# POWER.net
KiCad netlist of a schematic drawn in Altium Designer
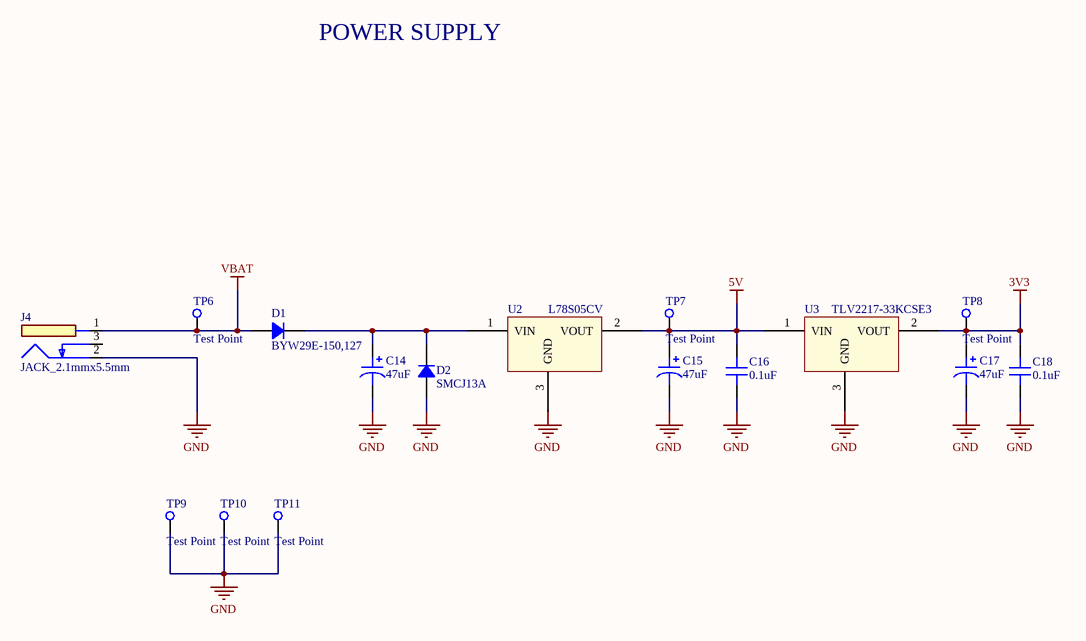
[diagram p0: POWER.SchDoc]

(export (version "E")
  (design (tool "Eeschema 10.0.6"))
  (components
    (comp (ref "C14")
      (value "47uF")
      (footprint "CAP_POL_D6.3MM_L5.8MM_H6.6MM")
      (description "CAP 47UF 35V ELECT WT SMD D6.3MM L5.8MM H 6.6MM")
      (fields (field (name "PART NUMBER") "UWT1V470MCL1GS") (field (name "VOLTAGE") "35V"))
      (libsource (lib "RespiradorLib") (part "C_POL_UWT1V470MCL1GS"))
    )
    (comp (ref "C15")
      (value "47uF")
      (footprint "CAP_POL_D6.3MM_L5.8MM_H6.6MM")
      (description "CAP 47UF 35V ELECT WT SMD D6.3MM L5.8MM H 6.6MM")
      (fields (field (name "PART NUMBER") "UWT1V470MCL1GS") (field (name "VOLTAGE") "35V"))
      (libsource (lib "RespiradorLib") (part "C_POL_UWT1V470MCL1GS"))
    )
    (comp (ref "C16")
      (value "0.1uF")
      (footprint "C_0805")
      (description "CAP CER .1UF 50V 10% X7R 080")
      (fields (field (name "PART NUMBER") "GRM21BR71H104KA01L") (field (name "VOLTAGE") "50V"))
      (libsource (lib "RespiradorLib") (part "C_0805_GRM21BR71H104KA01L"))
    )
    (comp (ref "C17")
      (value "47uF")
      (footprint "CAP_POL_D6.3MM_L5.8MM_H6.6MM")
      (description "CAP 47UF 35V ELECT WT SMD D6.3MM L5.8MM H 6.6MM")
      (fields (field (name "PART NUMBER") "UWT1V470MCL1GS") (field (name "VOLTAGE") "35V"))
      (libsource (lib "RespiradorLib") (part "C_POL_UWT1V470MCL1GS"))
    )
    (comp (ref "C18")
      (value "0.1uF")
      (footprint "C_0805")
      (description "CAP CER .1UF 50V 10% X7R 080")
      (fields (field (name "PART NUMBER") "GRM21BR71H104KA01L") (field (name "VOLTAGE") "50V"))
      (libsource (lib "RespiradorLib") (part "C_0805_GRM21BR71H104KA01L"))
    )
    (comp (ref "D1")
      (value "BYW29E-150,127")
      (footprint "TO-220-2")
      (description "DIODE RECT UFAST 150V TO220AC SOD59")
      (fields (field (name "VOLTAGE") "150V"))
      (libsource (lib "RespiradorLib") (part "DIODE_BYW29E-150,127"))
    )
    (comp (ref "D2")
      (value "SMCJ13A")
      (footprint "DO-214AB-2")
      (description "DIODE TVS 13V 1500W UNI 5% SMC DO-214AB-2_")
      (fields (field (name "VOLTAGE") "150V") (field (name "POWER") "1500W"))
      (libsource (lib "RespiradorLib") (part "DIODE_SMCJ13A"))
    )
    (comp (ref "J4")
      (value "JACK_2.1mmx5.5mm")
      (footprint "JACK_2.1mmx5.5mm")
      (description "Jack/Connector 2.1mm x 5.5mm")
      (fields (field (name "PART NUMBER") "CON-SOCJ-2155") (field (name "MANUFACTURER") "Gravitech"))
      (libsource (lib "RespiradorLib") (part "JACK_2.1mmx5.5mm"))
    )
    (comp (ref "TP6")
      (value "Test Point")
      (footprint "Test_Point")
      (libsource (lib "RespiradorLib") (part "Test Point"))
    )
    (comp (ref "TP7")
      (value "Test Point")
      (footprint "Test_Point")
      (libsource (lib "RespiradorLib") (part "Test Point"))
    )
    (comp (ref "TP8")
      (value "Test Point")
      (footprint "Test_Point")
      (libsource (lib "RespiradorLib") (part "Test Point"))
    )
    (comp (ref "TP9")
      (value "Test Point")
      (footprint "Test_Point")
      (libsource (lib "RespiradorLib") (part "Test Point"))
    )
    (comp (ref "TP10")
      (value "Test Point")
      (footprint "Test_Point")
      (libsource (lib "RespiradorLib") (part "Test Point"))
    )
    (comp (ref "TP11")
      (value "Test Point")
      (footprint "Test_Point")
      (libsource (lib "RespiradorLib") (part "Test Point"))
    )
    (comp (ref "U2")
      (value "L78S05CV")
      (footprint "TO-220")
      (description "IC REG POSITIVE 2A 5V TO-220")
      (libsource (lib "RespiradorLib") (part "REGULATOR_L78S05CV"))
    )
    (comp (ref "U3")
      (value "TLV2217-33KCSE3")
      (footprint "TO-220")
      (description "IC LDO REG FXDVOLT 3.3V TO-220")
      (libsource (lib "RespiradorLib") (part "REGULATOR_TLV2217"))
    )
  )
  (nets
    (net (code "1") (name "3V3") (class "Default")
      (node (ref "C17") (pin "1") (pinfunction "1_1") (pintype "passive"))
      (node (ref "C18") (pin "2") (pinfunction "2_2") (pintype "passive"))
      (node (ref "TP8") (pin "1") (pinfunction "TP_1") (pintype "passive"))
      (node (ref "U3") (pin "2") (pinfunction "VOUT_2") (pintype "passive"))
    )
    (net (code "2") (name "5V") (class "Default")
      (node (ref "C15") (pin "1") (pinfunction "1_1") (pintype "passive"))
      (node (ref "C16") (pin "2") (pinfunction "2_2") (pintype "passive"))
      (node (ref "TP7") (pin "1") (pinfunction "TP_1") (pintype "passive"))
      (node (ref "U2") (pin "2") (pinfunction "VOUT_2") (pintype "passive"))
      (node (ref "U3") (pin "1") (pinfunction "VIN_1") (pintype "passive"))
    )
    (net (code "3") (name "GND") (class "Default")
      (node (ref "C14") (pin "2") (pinfunction "2_2") (pintype "passive"))
      (node (ref "C15") (pin "2") (pinfunction "2_2") (pintype "passive"))
      (node (ref "C16") (pin "1") (pinfunction "1_1") (pintype "passive"))
      (node (ref "C17") (pin "2") (pinfunction "2_2") (pintype "passive"))
      (node (ref "C18") (pin "1") (pinfunction "1_1") (pintype "passive"))
      (node (ref "D2") (pin "1") (pinfunction "1_1") (pintype "passive"))
      (node (ref "J4") (pin "2") (pinfunction "2_2") (pintype "passive"))
      (node (ref "TP10") (pin "1") (pinfunction "TP_1") (pintype "passive"))
      (node (ref "TP11") (pin "1") (pinfunction "TP_1") (pintype "passive"))
      (node (ref "TP9") (pin "1") (pinfunction "TP_1") (pintype "passive"))
      (node (ref "U2") (pin "3") (pinfunction "GND_3") (pintype "passive"))
      (node (ref "U3") (pin "3") (pinfunction "GND_3") (pintype "passive"))
    )
    (net (code "4") (name "Net-(U2-VIN)") (class "Default")
      (node (ref "C14") (pin "1") (pinfunction "1_1") (pintype "passive"))
      (node (ref "D1") (pin "2") (pinfunction "2_2") (pintype "passive"))
      (node (ref "D2") (pin "2") (pinfunction "2_2") (pintype "passive"))
      (node (ref "U2") (pin "1") (pinfunction "VIN_1") (pintype "passive"))
    )
    (net (code "5") (name "VBAT") (class "Default")
      (node (ref "D1") (pin "1") (pinfunction "1_1") (pintype "passive"))
      (node (ref "J4") (pin "1") (pinfunction "1_1") (pintype "passive"))
      (node (ref "TP6") (pin "1") (pinfunction "TP_1") (pintype "passive"))
    )
    (net (code "6") (name "unconnected-(J4-Pad3)") (class "Default")
      (node (ref "J4") (pin "3") (pinfunction "3_3") (pintype "passive"))
    )
  )
)
